# Nano_BMS_Shield_v0_1.net
KiCad netlist of a schematic drawn in EAGLE
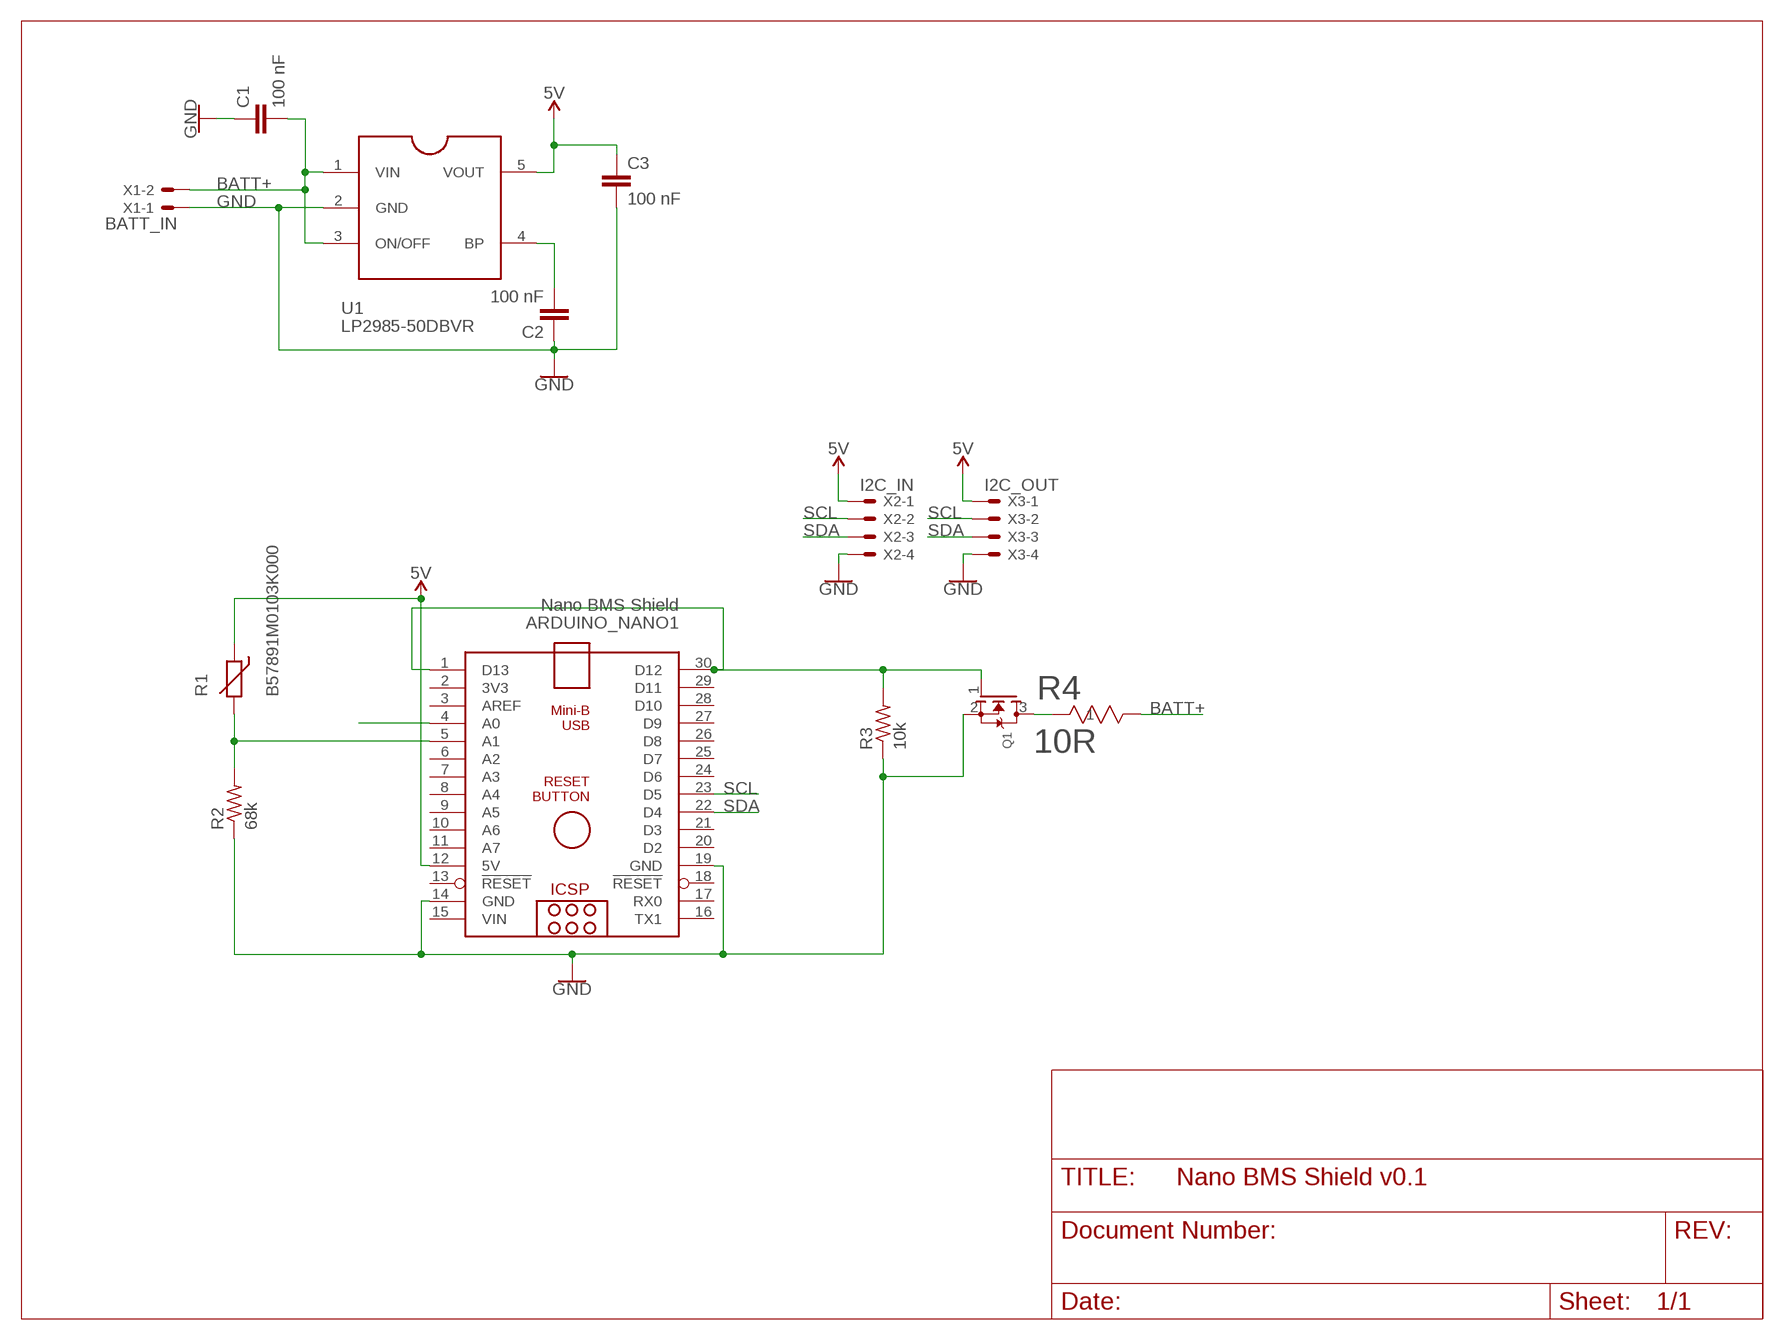
[diagram p0: schematic, sheet 1]

(export (version "E")
  (design (tool "Eeschema 10.0.6"))
  (components
    (comp (ref "ARDUINO_NANO1")
      (value "Nano BMS Shield")
      (footprint "eagle-import:ARDUINO_NANO")
      (libsource (lib "eagle-import") (part "ARDUINO_NANO"))
    )
    (comp (ref "C1")
      (value "100 nF")
      (footprint "eagle-import:C0603")
      (libsource (lib "eagle-import") (part "C-EUC0603"))
    )
    (comp (ref "C2")
      (value "100 nF")
      (footprint "eagle-import:C0603")
      (libsource (lib "eagle-import") (part "C-EUC0603"))
    )
    (comp (ref "C3")
      (value "100 nF")
      (footprint "eagle-import:C0603")
      (libsource (lib "eagle-import") (part "C-EUC0603"))
    )
    (comp (ref "Q1")
      (value "MOSFET-NREFLOW")
      (footprint "eagle-import:SOT23")
      (libsource (lib "eagle-import") (part "MOSFET-NREFLOW"))
    )
    (comp (ref "R1")
      (value "B57891M0103K000")
      (footprint "eagle-import:RS-2,5")
      (libsource (lib "eagle-import") (part "THERMISTOR-2,5"))
    )
    (comp (ref "R2")
      (value "68k")
      (footprint "eagle-import:R0603")
      (libsource (lib "eagle-import") (part "R-US_R0603"))
    )
    (comp (ref "R3")
      (value "10k")
      (footprint "eagle-import:R0603")
      (libsource (lib "eagle-import") (part "R-US_R0603"))
    )
    (comp (ref "R4")
      (value "10R")
      (footprint "eagle-import:YAG_FMP300")
      (fields (field (name "MANUFACTURER_PART_NUMBER") "FMP300JT7310R"))
      (libsource (lib "eagle-import") (part "FMP300JT-73-10R"))
    )
    (comp (ref "U1")
      (value "LP2985-50DBVR")
      (footprint "eagle-import:SOT23-5")
      (fields (field (name "MF") "Texas Instruments"))
      (libsource (lib "eagle-import") (part "LP2985-50DBVR"))
    )
    (comp (ref "X1")
      (value "BATT_IN")
      (footprint "eagle-import:JST-XH-02-PACKAGE-LONG-PAD")
      (libsource (lib "eagle-import") (part "JST-XH-02-PIN-LONG-PAD"))
    )
    (comp (ref "X2")
      (value "I2C_IN")
      (footprint "eagle-import:JST-XH-04-PACKAGE-LONG-PAD")
      (libsource (lib "eagle-import") (part "JST-XH-04-PIN-LONG-PAD"))
    )
    (comp (ref "X3")
      (value "I2C_OUT")
      (footprint "eagle-import:JST-XH-04-PACKAGE-LONG-PAD")
      (libsource (lib "eagle-import") (part "JST-XH-04-PIN-LONG-PAD"))
    )
  )
  (nets
    (net (code "1") (name "/BATT+") (class "Default")
      (node (ref "C1") (pin "2") (pinfunction "2_2") (pintype "passive"))
      (node (ref "R4") (pin "2") (pinfunction "2_2") (pintype "passive"))
      (node (ref "U1") (pin "1") (pinfunction "VIN_1") (pintype "input"))
      (node (ref "U1") (pin "3") (pinfunction "ON/OFF_3") (pintype "input"))
      (node (ref "X1") (pin "2") (pinfunction "S_2") (pintype "passive"))
    )
    (net (code "2") (name "/SCL") (class "Default")
      (node (ref "ARDUINO_NANO1") (pin "23") (pinfunction "D5_23") (pintype "bidirectional"))
      (node (ref "X2") (pin "2") (pinfunction "S_2") (pintype "passive"))
      (node (ref "X3") (pin "2") (pinfunction "S_2") (pintype "passive"))
    )
    (net (code "3") (name "/SDA") (class "Default")
      (node (ref "ARDUINO_NANO1") (pin "22") (pinfunction "D4_22") (pintype "bidirectional"))
      (node (ref "X2") (pin "3") (pinfunction "S_3") (pintype "passive"))
      (node (ref "X3") (pin "3") (pinfunction "S_3") (pintype "passive"))
    )
    (net (code "4") (name "/VIN") (class "Default")
      (node (ref "ARDUINO_NANO1") (pin "15") (pinfunction "VIN_15") (pintype "power_in"))
    )
    (net (code "5") (name "5V") (class "Default")
      (node (ref "ARDUINO_NANO1") (pin "12") (pinfunction "5V_12") (pintype "power_in"))
      (node (ref "C3") (pin "1") (pinfunction "1_1") (pintype "passive"))
      (node (ref "R1") (pin "1") (pinfunction "1_1") (pintype "passive"))
      (node (ref "U1") (pin "5") (pinfunction "VOUT_5") (pintype "output"))
      (node (ref "X2") (pin "1") (pinfunction "S_1") (pintype "passive"))
      (node (ref "X3") (pin "1") (pinfunction "S_1") (pintype "passive"))
    )
    (net (code "6") (name "GND") (class "Default")
      (node (ref "ARDUINO_NANO1") (pin "14") (pinfunction "GND_14") (pintype "power_in"))
      (node (ref "ARDUINO_NANO1") (pin "19") (pinfunction "GND_19") (pintype "power_in"))
      (node (ref "C1") (pin "1") (pinfunction "1_1") (pintype "passive"))
      (node (ref "C2") (pin "1") (pinfunction "1_1") (pintype "passive"))
      (node (ref "C3") (pin "2") (pinfunction "2_2") (pintype "passive"))
      (node (ref "Q1") (pin "2") (pinfunction "S_2") (pintype "bidirectional"))
      (node (ref "R2") (pin "1") (pinfunction "1_1") (pintype "passive"))
      (node (ref "R3") (pin "1") (pinfunction "1_1") (pintype "passive"))
      (node (ref "U1") (pin "2") (pinfunction "GND_2") (pintype "passive"))
      (node (ref "X1") (pin "1") (pinfunction "S_1") (pintype "passive"))
      (node (ref "X2") (pin "4") (pinfunction "S_4") (pintype "passive"))
      (node (ref "X3") (pin "4") (pinfunction "S_4") (pintype "passive"))
    )
    (net (code "7") (name "Net-(ARDUINO_NANO1-A1)") (class "Default")
      (node (ref "ARDUINO_NANO1") (pin "5") (pinfunction "A1_5") (pintype "bidirectional"))
      (node (ref "R1") (pin "2") (pinfunction "2_2") (pintype "passive"))
      (node (ref "R2") (pin "2") (pinfunction "2_2") (pintype "passive"))
    )
    (net (code "8") (name "Net-(ARDUINO_NANO1-D12)") (class "Default")
      (node (ref "ARDUINO_NANO1") (pin "1") (pinfunction "D13_1") (pintype "bidirectional"))
      (node (ref "ARDUINO_NANO1") (pin "30") (pinfunction "D12_30") (pintype "bidirectional"))
      (node (ref "Q1") (pin "1") (pinfunction "G_1") (pintype "bidirectional"))
      (node (ref "R3") (pin "2") (pinfunction "2_2") (pintype "passive"))
    )
    (net (code "9") (name "Net-(Q1-D)") (class "Default")
      (node (ref "Q1") (pin "3") (pinfunction "D_3") (pintype "bidirectional"))
      (node (ref "R4") (pin "1") (pinfunction "1_1") (pintype "passive"))
    )
    (net (code "10") (name "Net-(U1-BP)") (class "Default")
      (node (ref "C2") (pin "2") (pinfunction "2_2") (pintype "passive"))
      (node (ref "U1") (pin "4") (pinfunction "BP_4") (pintype "output"))
    )
    (net (code "11") (name "unconnected-(ARDUINO_NANO1-3V3-Pad2)") (class "Default")
      (node (ref "ARDUINO_NANO1") (pin "2") (pinfunction "3V3_2") (pintype "output"))
    )
    (net (code "12") (name "unconnected-(ARDUINO_NANO1-A0-Pad4)") (class "Default")
      (node (ref "ARDUINO_NANO1") (pin "4") (pinfunction "A0_4") (pintype "bidirectional"))
    )
    (net (code "13") (name "unconnected-(ARDUINO_NANO1-A2-Pad6)") (class "Default")
      (node (ref "ARDUINO_NANO1") (pin "6") (pinfunction "A2_6") (pintype "bidirectional"))
    )
    (net (code "14") (name "unconnected-(ARDUINO_NANO1-A3-Pad7)") (class "Default")
      (node (ref "ARDUINO_NANO1") (pin "7") (pinfunction "A3_7") (pintype "bidirectional"))
    )
    (net (code "15") (name "unconnected-(ARDUINO_NANO1-A4-Pad8)") (class "Default")
      (node (ref "ARDUINO_NANO1") (pin "8") (pinfunction "A4_8") (pintype "bidirectional"))
    )
    (net (code "16") (name "unconnected-(ARDUINO_NANO1-A5-Pad9)") (class "Default")
      (node (ref "ARDUINO_NANO1") (pin "9") (pinfunction "A5_9") (pintype "bidirectional"))
    )
    (net (code "17") (name "unconnected-(ARDUINO_NANO1-A6-Pad10)") (class "Default")
      (node (ref "ARDUINO_NANO1") (pin "10") (pinfunction "A6_10") (pintype "bidirectional"))
    )
    (net (code "18") (name "unconnected-(ARDUINO_NANO1-A7-Pad11)") (class "Default")
      (node (ref "ARDUINO_NANO1") (pin "11") (pinfunction "A7_11") (pintype "bidirectional"))
    )
    (net (code "19") (name "unconnected-(ARDUINO_NANO1-AREF-Pad3)") (class "Default")
      (node (ref "ARDUINO_NANO1") (pin "3") (pinfunction "AREF_3") (pintype "input"))
    )
    (net (code "20") (name "unconnected-(ARDUINO_NANO1-D2-Pad20)") (class "Default")
      (node (ref "ARDUINO_NANO1") (pin "20") (pinfunction "D2_20") (pintype "bidirectional"))
    )
    (net (code "21") (name "unconnected-(ARDUINO_NANO1-D3-Pad21)") (class "Default")
      (node (ref "ARDUINO_NANO1") (pin "21") (pinfunction "D3_21") (pintype "bidirectional"))
    )
    (net (code "22") (name "unconnected-(ARDUINO_NANO1-D6-Pad24)") (class "Default")
      (node (ref "ARDUINO_NANO1") (pin "24") (pinfunction "D6_24") (pintype "bidirectional"))
    )
    (net (code "23") (name "unconnected-(ARDUINO_NANO1-D7-Pad25)") (class "Default")
      (node (ref "ARDUINO_NANO1") (pin "25") (pinfunction "D7_25") (pintype "bidirectional"))
    )
    (net (code "24") (name "unconnected-(ARDUINO_NANO1-D8-Pad26)") (class "Default")
      (node (ref "ARDUINO_NANO1") (pin "26") (pinfunction "D8_26") (pintype "bidirectional"))
    )
    (net (code "25") (name "unconnected-(ARDUINO_NANO1-D9-Pad27)") (class "Default")
      (node (ref "ARDUINO_NANO1") (pin "27") (pinfunction "D9_27") (pintype "bidirectional"))
    )
    (net (code "26") (name "unconnected-(ARDUINO_NANO1-D10-Pad28)") (class "Default")
      (node (ref "ARDUINO_NANO1") (pin "28") (pinfunction "D10_28") (pintype "bidirectional"))
    )
    (net (code "27") (name "unconnected-(ARDUINO_NANO1-D11-Pad29)") (class "Default")
      (node (ref "ARDUINO_NANO1") (pin "29") (pinfunction "D11_29") (pintype "bidirectional"))
    )
    (net (code "28") (name "unconnected-(ARDUINO_NANO1-RX0-Pad17)") (class "Default")
      (node (ref "ARDUINO_NANO1") (pin "17") (pinfunction "RX0_17") (pintype "bidirectional"))
    )
    (net (code "29") (name "unconnected-(ARDUINO_NANO1-TX1-Pad16)") (class "Default")
      (node (ref "ARDUINO_NANO1") (pin "16") (pinfunction "TX1_16") (pintype "bidirectional"))
    )
    (net (code "30") (name "unconnected-(ARDUINO_NANO1-~{RESET}-Pad13)") (class "Default")
      (node (ref "ARDUINO_NANO1") (pin "13") (pinfunction "~{RESET}_13") (pintype "input"))
    )
    (net (code "31") (name "unconnected-(ARDUINO_NANO1-~{RESET}-Pad18)") (class "Default")
      (node (ref "ARDUINO_NANO1") (pin "18") (pinfunction "~{RESET}_18") (pintype "input"))
    )
  )
)
